# CON_PCI_Express_X1_36PIN.net
KiCad netlist of a schematic drawn in Altium Designer
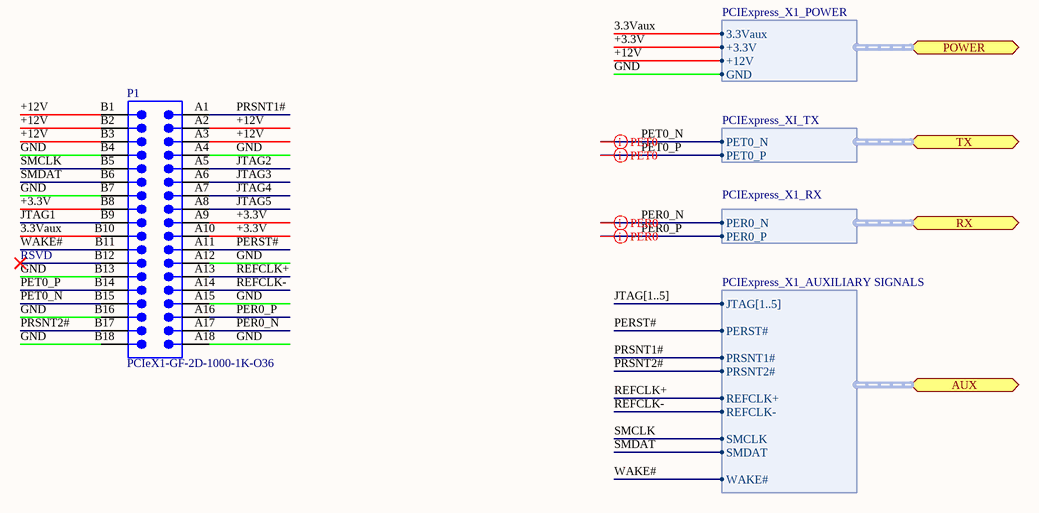
[diagram p0: CON_PCI_Express_X1_36PIN.SchDoc]

(export (version "E")
  (design (tool "Eeschema 10.0.6"))
  (components
    (comp (ref "P1")
      (value "PCIeX1-GF-2D-1000-1K-O36")
      (footprint "PCIeX1-GF-2D-1000-1K-O36")
      (description "Golden finger, PCIeX1, Dual, Opposite, Pitch 1mm, 36-Position")
      (fields (field (name "PUBLISHER") "Altium"))
      (libsource (lib "Altium Shanghai") (part "PCIeX1-GF-2D-1000-1K-O36"))
    )
  )
  (nets
    (net (code "6") (name "/+3.3V") (class "Default")
      (node (ref "P1") (pin "A10") (pinfunction "A10_A10") (pintype "passive"))
      (node (ref "P1") (pin "A9") (pinfunction "A9_A9") (pintype "passive"))
      (node (ref "P1") (pin "B8") (pinfunction "B8_B8") (pintype "passive"))
    )
    (net (code "7") (name "/+12V") (class "Default")
      (node (ref "P1") (pin "A2") (pinfunction "A2_A2") (pintype "passive"))
      (node (ref "P1") (pin "A3") (pinfunction "A3_A3") (pintype "passive"))
      (node (ref "P1") (pin "B1") (pinfunction "B1_B1") (pintype "passive"))
      (node (ref "P1") (pin "B2") (pinfunction "B2_B2") (pintype "passive"))
      (node (ref "P1") (pin "B3") (pinfunction "B3_B3") (pintype "passive"))
    )
    (net (code "8") (name "/3.3Vaux") (class "Default")
      (node (ref "P1") (pin "B10") (pinfunction "B10_B10") (pintype "passive"))
    )
    (net (code "9") (name "/GND") (class "Default")
      (node (ref "P1") (pin "A12") (pinfunction "A12_A12") (pintype "passive"))
      (node (ref "P1") (pin "A15") (pinfunction "A15_A15") (pintype "passive"))
      (node (ref "P1") (pin "A18") (pinfunction "A18_A18") (pintype "passive"))
      (node (ref "P1") (pin "A4") (pinfunction "A4_A4") (pintype "passive"))
      (node (ref "P1") (pin "B13") (pinfunction "B13_B13") (pintype "passive"))
      (node (ref "P1") (pin "B16") (pinfunction "B16_B16") (pintype "passive"))
      (node (ref "P1") (pin "B18") (pinfunction "B18_B18") (pintype "passive"))
      (node (ref "P1") (pin "B4") (pinfunction "B4_B4") (pintype "passive"))
      (node (ref "P1") (pin "B7") (pinfunction "B7_B7") (pintype "passive"))
    )
    (net (code "10") (name "/JTAG1") (class "Default")
      (node (ref "P1") (pin "B9") (pinfunction "B9_B9") (pintype "passive"))
    )
    (net (code "11") (name "/JTAG2") (class "Default")
      (node (ref "P1") (pin "A5") (pinfunction "A5_A5") (pintype "passive"))
    )
    (net (code "12") (name "/JTAG3") (class "Default")
      (node (ref "P1") (pin "A6") (pinfunction "A6_A6") (pintype "passive"))
    )
    (net (code "13") (name "/JTAG4") (class "Default")
      (node (ref "P1") (pin "A7") (pinfunction "A7_A7") (pintype "passive"))
    )
    (net (code "14") (name "/JTAG5") (class "Default")
      (node (ref "P1") (pin "A8") (pinfunction "A8_A8") (pintype "passive"))
    )
    (net (code "16") (name "/PER0_N") (class "Default")
      (node (ref "P1") (pin "A17") (pinfunction "A17_A17") (pintype "passive"))
    )
    (net (code "17") (name "/PER0_P") (class "Default")
      (node (ref "P1") (pin "A16") (pinfunction "A16_A16") (pintype "passive"))
    )
    (net (code "18") (name "/PERST#") (class "Default")
      (node (ref "P1") (pin "A11") (pinfunction "A11_A11") (pintype "passive"))
    )
    (net (code "19") (name "/PET0_N") (class "Default")
      (node (ref "P1") (pin "B15") (pinfunction "B15_B15") (pintype "passive"))
    )
    (net (code "20") (name "/PET0_P") (class "Default")
      (node (ref "P1") (pin "B14") (pinfunction "B14_B14") (pintype "passive"))
    )
    (net (code "21") (name "/PRSNT1#") (class "Default")
      (node (ref "P1") (pin "A1") (pinfunction "A1_A1") (pintype "passive"))
    )
    (net (code "22") (name "/PRSNT2#") (class "Default")
      (node (ref "P1") (pin "B17") (pinfunction "B17_B17") (pintype "passive"))
    )
    (net (code "23") (name "/REFCLK+") (class "Default")
      (node (ref "P1") (pin "A13") (pinfunction "A13_A13") (pintype "passive"))
    )
    (net (code "24") (name "/REFCLK-") (class "Default")
      (node (ref "P1") (pin "A14") (pinfunction "A14_A14") (pintype "passive"))
    )
    (net (code "25") (name "/SMCLK") (class "Default")
      (node (ref "P1") (pin "B5") (pinfunction "B5_B5") (pintype "passive"))
    )
    (net (code "26") (name "/SMDAT") (class "Default")
      (node (ref "P1") (pin "B6") (pinfunction "B6_B6") (pintype "passive"))
    )
    (net (code "27") (name "/WAKE#") (class "Default")
      (node (ref "P1") (pin "B11") (pinfunction "B11_B11") (pintype "passive"))
    )
    (net (code "32") (name "unconnected-(P1-PadB12)") (class "Default")
      (node (ref "P1") (pin "B12") (pinfunction "B12_B12") (pintype "passive+no_connect"))
    )
  )
)
